# Sheet_2812b.net
KiCad netlist of a schematic drawn in Altium Designer
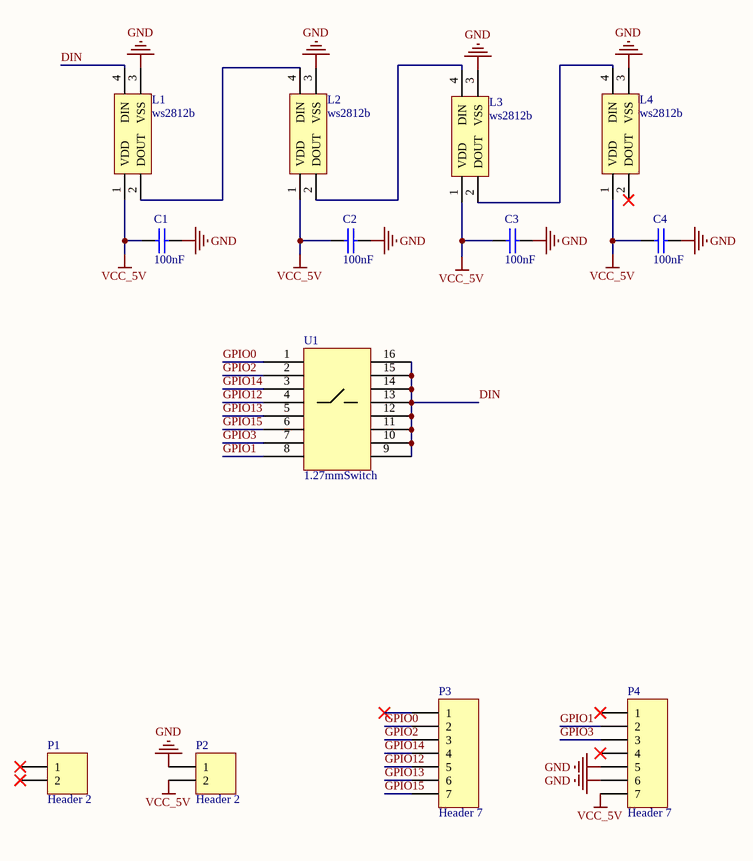
[diagram p0: Sheet_2812b.SchDoc]

(export (version "E")
  (design (tool "Eeschema 10.0.6"))
  (components
    (comp (ref "C1")
      (value "100nF")
      (footprint "C0603")
      (description "贴片电容")
      (libsource (lib "Schlib_OLEDMCU") (part "C0603"))
    )
    (comp (ref "C2")
      (value "100nF")
      (footprint "C0603")
      (description "贴片电容")
      (libsource (lib "Schlib_OLEDMCU") (part "C0603"))
    )
    (comp (ref "C3")
      (value "100nF")
      (footprint "C0603")
      (description "贴片电容")
      (libsource (lib "Schlib_OLEDMCU") (part "C0603"))
    )
    (comp (ref "C4")
      (value "100nF")
      (footprint "C0603")
      (description "贴片电容")
      (libsource (lib "Schlib_OLEDMCU") (part "C0603"))
    )
    (comp (ref "L1")
      (value "ws2812b")
      (footprint "ws2812b")
      (description "RGB灯珠")
      (libsource (lib "Schlib_OLEDMCU") (part "ws2812b"))
    )
    (comp (ref "L2")
      (value "ws2812b")
      (footprint "ws2812b")
      (description "RGB灯珠")
      (libsource (lib "Schlib_OLEDMCU") (part "ws2812b"))
    )
    (comp (ref "L3")
      (value "ws2812b")
      (footprint "ws2812b")
      (description "RGB灯珠")
      (libsource (lib "Schlib_OLEDMCU") (part "ws2812b"))
    )
    (comp (ref "L4")
      (value "ws2812b")
      (footprint "ws2812b")
      (description "RGB灯珠")
      (libsource (lib "Schlib_OLEDMCU") (part "ws2812b"))
    )
    (comp (ref "P1")
      (value "Header 2")
      (footprint "HDR1X2")
      (description "Header, 2-Pin")
      (fields (field (name "PUBLISHER") "Altium Limited"))
      (libsource (lib "Miscellaneous Connectors") (part "Header 2"))
    )
    (comp (ref "P2")
      (value "Header 2")
      (footprint "HDR1X2")
      (description "Header, 2-Pin")
      (fields (field (name "PUBLISHER") "Altium Limited"))
      (libsource (lib "Miscellaneous Connectors") (part "Header 2"))
    )
    (comp (ref "P3")
      (value "Header 7")
      (footprint "HDR1X7")
      (description "Header, 7-Pin")
      (fields (field (name "PUBLISHER") "Altium Limited"))
      (libsource (lib "Miscellaneous Connectors") (part "Header 7"))
    )
    (comp (ref "P4")
      (value "Header 7")
      (footprint "HDR1X7")
      (description "Header, 7-Pin")
      (fields (field (name "PUBLISHER") "Altium Limited"))
      (libsource (lib "Miscellaneous Connectors") (part "Header 7"))
    )
    (comp (ref "U1")
      (value "1.27mmSwitch")
      (footprint "NumberSwitch")
      (description "拨码开关")
      (libsource (lib "Schlib_OLEDMCU") (part "NumberSwitch"))
    )
  )
  (nets
    (net (code "1") (name "/DIN") (class "Default")
      (node (ref "L1") (pin "4") (pinfunction "DIN_4") (pintype "passive"))
      (node (ref "U1") (pin "10") (pinfunction "10_10") (pintype "passive"))
      (node (ref "U1") (pin "11") (pinfunction "11_11") (pintype "passive"))
      (node (ref "U1") (pin "12") (pinfunction "12_12") (pintype "passive"))
      (node (ref "U1") (pin "13") (pinfunction "13_13") (pintype "passive"))
      (node (ref "U1") (pin "14") (pinfunction "14_14") (pintype "passive"))
      (node (ref "U1") (pin "15") (pinfunction "15_15") (pintype "passive"))
      (node (ref "U1") (pin "16") (pinfunction "16_16") (pintype "passive"))
      (node (ref "U1") (pin "9") (pinfunction "9_9") (pintype "passive"))
    )
    (net (code "2") (name "/GPIO0") (class "Default")
      (node (ref "P3") (pin "2") (pinfunction "2_2") (pintype "passive"))
      (node (ref "U1") (pin "1") (pinfunction "1_1") (pintype "passive"))
    )
    (net (code "3") (name "/GPIO1") (class "Default")
      (node (ref "P4") (pin "2") (pinfunction "2_2") (pintype "passive"))
      (node (ref "U1") (pin "8") (pinfunction "8_8") (pintype "passive"))
    )
    (net (code "4") (name "/GPIO2") (class "Default")
      (node (ref "P3") (pin "3") (pinfunction "3_3") (pintype "passive"))
      (node (ref "U1") (pin "2") (pinfunction "2_2") (pintype "passive"))
    )
    (net (code "5") (name "/GPIO3") (class "Default")
      (node (ref "P4") (pin "3") (pinfunction "3_3") (pintype "passive"))
      (node (ref "U1") (pin "7") (pinfunction "7_7") (pintype "passive"))
    )
    (net (code "6") (name "/GPIO12") (class "Default")
      (node (ref "P3") (pin "5") (pinfunction "5_5") (pintype "passive"))
      (node (ref "U1") (pin "4") (pinfunction "4_4") (pintype "passive"))
    )
    (net (code "7") (name "/GPIO13") (class "Default")
      (node (ref "P3") (pin "6") (pinfunction "6_6") (pintype "passive"))
      (node (ref "U1") (pin "5") (pinfunction "5_5") (pintype "passive"))
    )
    (net (code "8") (name "/GPIO14") (class "Default")
      (node (ref "P3") (pin "4") (pinfunction "4_4") (pintype "passive"))
      (node (ref "U1") (pin "3") (pinfunction "3_3") (pintype "passive"))
    )
    (net (code "9") (name "/GPIO15") (class "Default")
      (node (ref "P3") (pin "7") (pinfunction "7_7") (pintype "passive"))
      (node (ref "U1") (pin "6") (pinfunction "6_6") (pintype "passive"))
    )
    (net (code "10") (name "GND") (class "Default")
      (node (ref "C1") (pin "2") (pinfunction "2_2") (pintype "passive"))
      (node (ref "C2") (pin "2") (pinfunction "2_2") (pintype "passive"))
      (node (ref "C3") (pin "2") (pinfunction "2_2") (pintype "passive"))
      (node (ref "C4") (pin "2") (pinfunction "2_2") (pintype "passive"))
      (node (ref "L1") (pin "3") (pinfunction "VSS_3") (pintype "passive"))
      (node (ref "L2") (pin "3") (pinfunction "VSS_3") (pintype "passive"))
      (node (ref "L3") (pin "3") (pinfunction "VSS_3") (pintype "passive"))
      (node (ref "L4") (pin "3") (pinfunction "VSS_3") (pintype "passive"))
      (node (ref "P2") (pin "1") (pinfunction "1_1") (pintype "passive"))
      (node (ref "P4") (pin "5") (pinfunction "5_5") (pintype "passive"))
      (node (ref "P4") (pin "6") (pinfunction "6_6") (pintype "passive"))
    )
    (net (code "11") (name "Net-(L1-DOUT)") (class "Default")
      (node (ref "L1") (pin "2") (pinfunction "DOUT_2") (pintype "passive"))
      (node (ref "L2") (pin "4") (pinfunction "DIN_4") (pintype "passive"))
    )
    (net (code "12") (name "Net-(L2-DOUT)") (class "Default")
      (node (ref "L2") (pin "2") (pinfunction "DOUT_2") (pintype "passive"))
      (node (ref "L3") (pin "4") (pinfunction "DIN_4") (pintype "passive"))
    )
    (net (code "13") (name "Net-(L3-DOUT)") (class "Default")
      (node (ref "L3") (pin "2") (pinfunction "DOUT_2") (pintype "passive"))
      (node (ref "L4") (pin "4") (pinfunction "DIN_4") (pintype "passive"))
    )
    (net (code "14") (name "VCC_5V") (class "Default")
      (node (ref "C1") (pin "1") (pinfunction "1_1") (pintype "passive"))
      (node (ref "C2") (pin "1") (pinfunction "1_1") (pintype "passive"))
      (node (ref "C3") (pin "1") (pinfunction "1_1") (pintype "passive"))
      (node (ref "C4") (pin "1") (pinfunction "1_1") (pintype "passive"))
      (node (ref "L1") (pin "1") (pinfunction "VDD_1") (pintype "passive"))
      (node (ref "L2") (pin "1") (pinfunction "VDD_1") (pintype "passive"))
      (node (ref "L3") (pin "1") (pinfunction "VDD_1") (pintype "passive"))
      (node (ref "L4") (pin "1") (pinfunction "VDD_1") (pintype "passive"))
      (node (ref "P2") (pin "2") (pinfunction "2_2") (pintype "passive"))
      (node (ref "P4") (pin "7") (pinfunction "7_7") (pintype "passive"))
    )
    (net (code "15") (name "unconnected-(L4-DOUT-Pad2)") (class "Default")
      (node (ref "L4") (pin "2") (pinfunction "DOUT_2") (pintype "passive+no_connect"))
    )
    (net (code "16") (name "unconnected-(P1-Pad1)") (class "Default")
      (node (ref "P1") (pin "1") (pinfunction "1_1") (pintype "passive+no_connect"))
    )
    (net (code "17") (name "unconnected-(P1-Pad2)") (class "Default")
      (node (ref "P1") (pin "2") (pinfunction "2_2") (pintype "passive+no_connect"))
    )
    (net (code "18") (name "unconnected-(P3-Pad1)") (class "Default")
      (node (ref "P3") (pin "1") (pinfunction "1_1") (pintype "passive+no_connect"))
    )
    (net (code "19") (name "unconnected-(P4-Pad1)") (class "Default")
      (node (ref "P4") (pin "1") (pinfunction "1_1") (pintype "passive+no_connect"))
    )
    (net (code "20") (name "unconnected-(P4-Pad4)") (class "Default")
      (node (ref "P4") (pin "4") (pinfunction "4_4") (pintype "passive+no_connect"))
    )
  )
)
